# BOOST_CONVERTER.net
KiCad netlist of a schematic drawn in Altium Designer
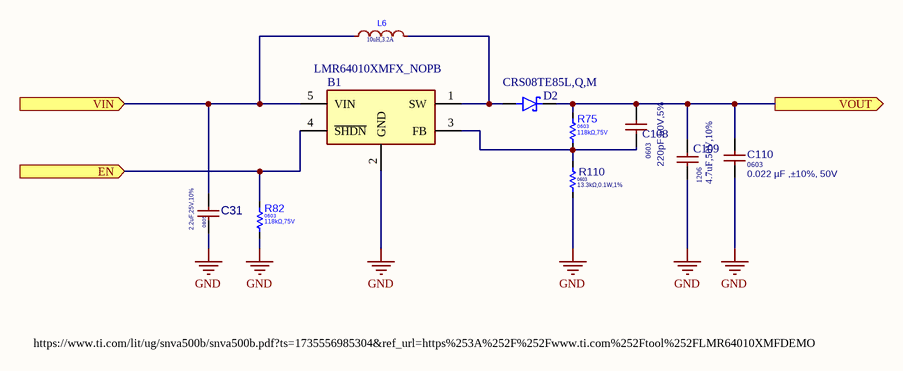
[diagram p0: BOOST_CONVERTER.SchDoc]

(export (version "E")
  (design (tool "Eeschema 10.0.6"))
  (components
    (comp (ref "B1")
      (value "LMR64010XMFX_NOPB")
      (footprint "SOT95P280X145-5N")
      (description "SIMPLE SWITCHER 2.7V to 14V, 1A Step-Up Regulator in SOT-23 Package")
      (fields
        (field (name "MOUSER PART NUMBER") "926-LMR64010XMFXNOPB")
        (field (name "MANUFACTURER_PART_NUMBER") "LMR64010XMFX/NOPB")
      )
      (libsource (lib "IC") (part "LMR64010XMFX_NOPB"))
    )
    (comp (ref "C31")
      (value "2.2uF,25V,10%")
      (footprint "C0805")
      (description "CAP CER 2.2UF 25V X7R 10% 0805")
      (fields
        (field (name "MANUFACTURER") "Samsung")
        (field (name "MPN") "CL21B225KAFNNNE")
        (field (name "PACKAGE") "0805")
      )
      (libsource (lib "RCL") (part "CAP_Template_0805"))
    )
    (comp (ref "C108")
      (value "220pF,50V,5%")
      (footprint "C0603")
      (description "220 pF ±5% 50V Ceramic Capacitor C0G, NP0 0603 (1608 Metric)")
      (fields
        (field (name "MPN") "C0603C221J5GACTU")
        (field (name "MANUFACTURER") "KEMET")
        (field (name "PACKAGE") "0603")
      )
      (libsource (lib "RCL") (part "C0603C221J5GACTU"))
    )
    (comp (ref "C109")
      (value "4.7uF,50V,10%")
      (footprint "C1206")
      (description "4.7 µF ±10% 50V Ceramic Capacitor X7R 1210 (3225 Metric)")
      (fields
        (field (name "MANUFACTURER") "Murata Electronics")
        (field (name "MPN") "GRM32ER71H475KA88L")
        (field (name "PACKAGE") "1206")
      )
      (libsource (lib "RCL") (part "GRM32ER71H475KA88L"))
    )
    (comp (ref "C110")
      (value "0.022 µF ,±10%, 50V")
      (footprint "C0603")
      (description "0.022 µF ±10% 50V Ceramic Capacitor X7R 0603 (1608 Metric)")
      (fields
        (field (name "MPN") "GRM188R71H223KA01D")
        (field (name "MANUFACTURER") "Murata Electronics")
        (field (name "PACKAGE") "0603")
      )
      (libsource (lib "RCL") (part "GRM188R71H223KA01D"))
    )
    (comp (ref "D2")
      (value "CRS08TE85L,Q,M")
      (footprint "S-FLAT_TOS")
      (description "DIODE SCHOTTKY 30V 1.5A S-FLAT")
      (fields (field (name "MPN") "CRS08(TE85L,Q,M)"))
      (libsource (lib "RCL") (part "CRS08TE85L,Q,M"))
    )
    (comp (ref "L6")
      (value "10uH,3.2A")
      (footprint "inductor_SMD,5.2x5.4mm")
      (description "3.2A 10uH Integrated molded inductor ±20% 3.5A SMD,5.2x5.4mm Power Inductors ROHS")
      (fields (field (name "MANUFACTURER") "cjiang") (field (name "MPN") "FXL0530-100-M"))
      (libsource (lib "RCL") (part "FXL0530-100-M"))
    )
    (comp (ref "R75")
      (value "118kΩ,75V")
      (footprint "R0603")
      (description "100mW Thick Film Resistors 75V ±100ppm/℃ ±1% 118kΩ 0603 Chip Resistor - Surface Mount ROHS")
      (fields
        (field (name "MANUFACTURER") "UNI-ROYAL")
        (field (name "MPN") "0603WAF1183T5E")
        (field (name "PACKAGE") "0603")
      )
      (libsource (lib "RCL") (part "0603WAF1183T5E"))
    )
    (comp (ref "R82")
      (value "118kΩ,75V")
      (footprint "R0603")
      (description "100mW Thick Film Resistors 75V ±100ppm/℃ ±1% 118kΩ 0603 Chip Resistor - Surface Mount ROHS")
      (fields
        (field (name "MANUFACTURER") "UNI-ROYAL")
        (field (name "MPN") "0603WAF1183T5E")
        (field (name "PACKAGE") "0603")
      )
      (libsource (lib "RCL") (part "0603WAF1183T5E"))
    )
    (comp (ref "R110")
      (value "13.3kΩ,0.1W,1%")
      (footprint "R0603")
      (description "13.3 kOhms ±1% 0.1W, 1/10W Chip Resistor 0603 (1608 Metric) Automotive AEC-Q200 Thick Film")
      (fields
        (field (name "MPN") "CRCW060313K3FKEA")
        (field (name "MANUFACTURER") "Vishay Dale")
        (field (name "PACKAGE") "0603")
      )
      (libsource (lib "RCL") (part "CRCW060313K3FKEA"))
    )
  )
  (nets
    (net (code "1") (name "/EN") (class "Default")
      (node (ref "B1") (pin "4") (pinfunction "~{SHDN}_4") (pintype "passive"))
      (node (ref "R82") (pin "1") (pinfunction "1_1") (pintype "passive"))
    )
    (net (code "2") (name "/VIN") (class "Default")
      (node (ref "B1") (pin "5") (pinfunction "VIN_5") (pintype "passive"))
      (node (ref "C31") (pin "2") (pinfunction "2_2") (pintype "passive"))
      (node (ref "L6") (pin "1") (pinfunction "1_1") (pintype "passive"))
    )
    (net (code "3") (name "/VOUT") (class "Default")
      (node (ref "C108") (pin "2") (pinfunction "2_2") (pintype "passive"))
      (node (ref "C109") (pin "2") (pinfunction "2_2") (pintype "passive"))
      (node (ref "C110") (pin "2") (pinfunction "2_2") (pintype "passive"))
      (node (ref "D2") (pin "2") (pinfunction "K_2") (pintype "passive"))
      (node (ref "R75") (pin "1") (pinfunction "1_1") (pintype "passive"))
    )
    (net (code "4") (name "GND") (class "Default")
      (node (ref "B1") (pin "2") (pinfunction "GND_2") (pintype "passive"))
      (node (ref "C109") (pin "1") (pinfunction "1_1") (pintype "passive"))
      (node (ref "C110") (pin "1") (pinfunction "1_1") (pintype "passive"))
      (node (ref "C31") (pin "1") (pinfunction "1_1") (pintype "passive"))
      (node (ref "R110") (pin "1") (pinfunction "1_1") (pintype "passive"))
      (node (ref "R82") (pin "2") (pinfunction "2_2") (pintype "passive"))
    )
    (net (code "5") (name "Net-(B1-FB)") (class "Default")
      (node (ref "B1") (pin "3") (pinfunction "FB_3") (pintype "passive"))
      (node (ref "C108") (pin "1") (pinfunction "1_1") (pintype "passive"))
      (node (ref "R110") (pin "2") (pinfunction "2_2") (pintype "passive"))
      (node (ref "R75") (pin "2") (pinfunction "2_2") (pintype "passive"))
    )
    (net (code "6") (name "Net-(B1-SW)") (class "Default")
      (node (ref "B1") (pin "1") (pinfunction "SW_1") (pintype "passive"))
      (node (ref "D2") (pin "1") (pinfunction "A_1") (pintype "passive"))
      (node (ref "L6") (pin "2") (pinfunction "2_2") (pintype "passive"))
    )
  )
)
